# 09_USB.net
KiCad netlist of a schematic drawn in Altium Designer
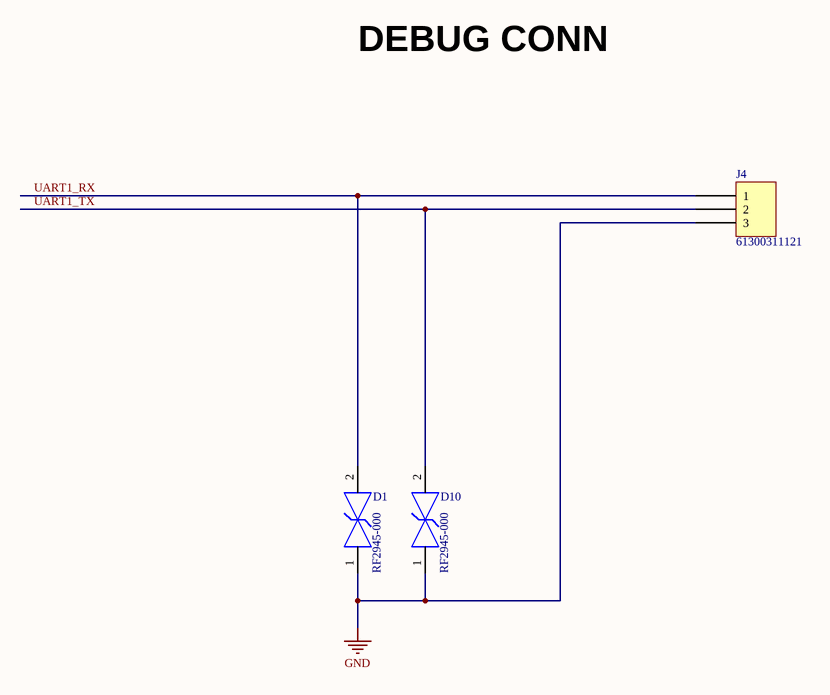
[diagram p0: 09_USB.SchDoc]

(export (version "E")
  (design (tool "Eeschema 10.0.6"))
  (components
    (comp (ref "D1")
      (value "RF2945-000")
      (footprint "FP-SESD0402-MFG")
      (description "TVS DIODE 7V 10V 0402")
      (fields
        (field (name "OCTOPART") "https://octopart.com/rf2945-000-littelfuse-56516902")
        (field (name "MANUFACTURER") "Littelfuse")
      )
      (libsource (lib "Altium Content Vault") (part "876f4347bf90aa6f500f43e3cd03972"))
    )
    (comp (ref "D10")
      (value "RF2945-000")
      (footprint "FP-SESD0402-MFG")
      (description "TVS DIODE 7V 10V 0402")
      (fields
        (field (name "OCTOPART") "https://octopart.com/rf2945-000-littelfuse-56516902")
        (field (name "MANUFACTURER") "Littelfuse")
      )
      (libsource (lib "Altium Content Vault") (part "876f4347bf90aa6f500f43e3cd03972"))
    )
    (comp (ref "J4")
      (value "61300311121")
      (footprint "WURTH WE-PHD 61300311121")
      (description "CONN HEADER VERT 3POS 2.54MM")
      (fields (field (name "MANUFACTURER") "Würth Elektronik"))
      (libsource (lib "Celestial Altium Library - altium_library") (part "3 Pin"))
    )
  )
  (nets
    (net (code "1") (name "/UART1_RX") (class "Default")
      (node (ref "D1") (pin "2") (pinfunction "2_2") (pintype "passive"))
      (node (ref "J4") (pin "1") (pinfunction "1_1") (pintype "passive"))
    )
    (net (code "2") (name "/UART1_TX") (class "Default")
      (node (ref "D10") (pin "2") (pinfunction "2_2") (pintype "passive"))
      (node (ref "J4") (pin "2") (pinfunction "2_2") (pintype "passive"))
    )
    (net (code "3") (name "GND") (class "Default")
      (node (ref "D1") (pin "1") (pinfunction "1_1") (pintype "passive"))
      (node (ref "D10") (pin "1") (pinfunction "1_1") (pintype "passive"))
      (node (ref "J4") (pin "3") (pinfunction "3_3") (pintype "passive"))
    )
  )
)
